# Chime_PCB_v2.net
KiCad netlist of a schematic drawn in EAGLE
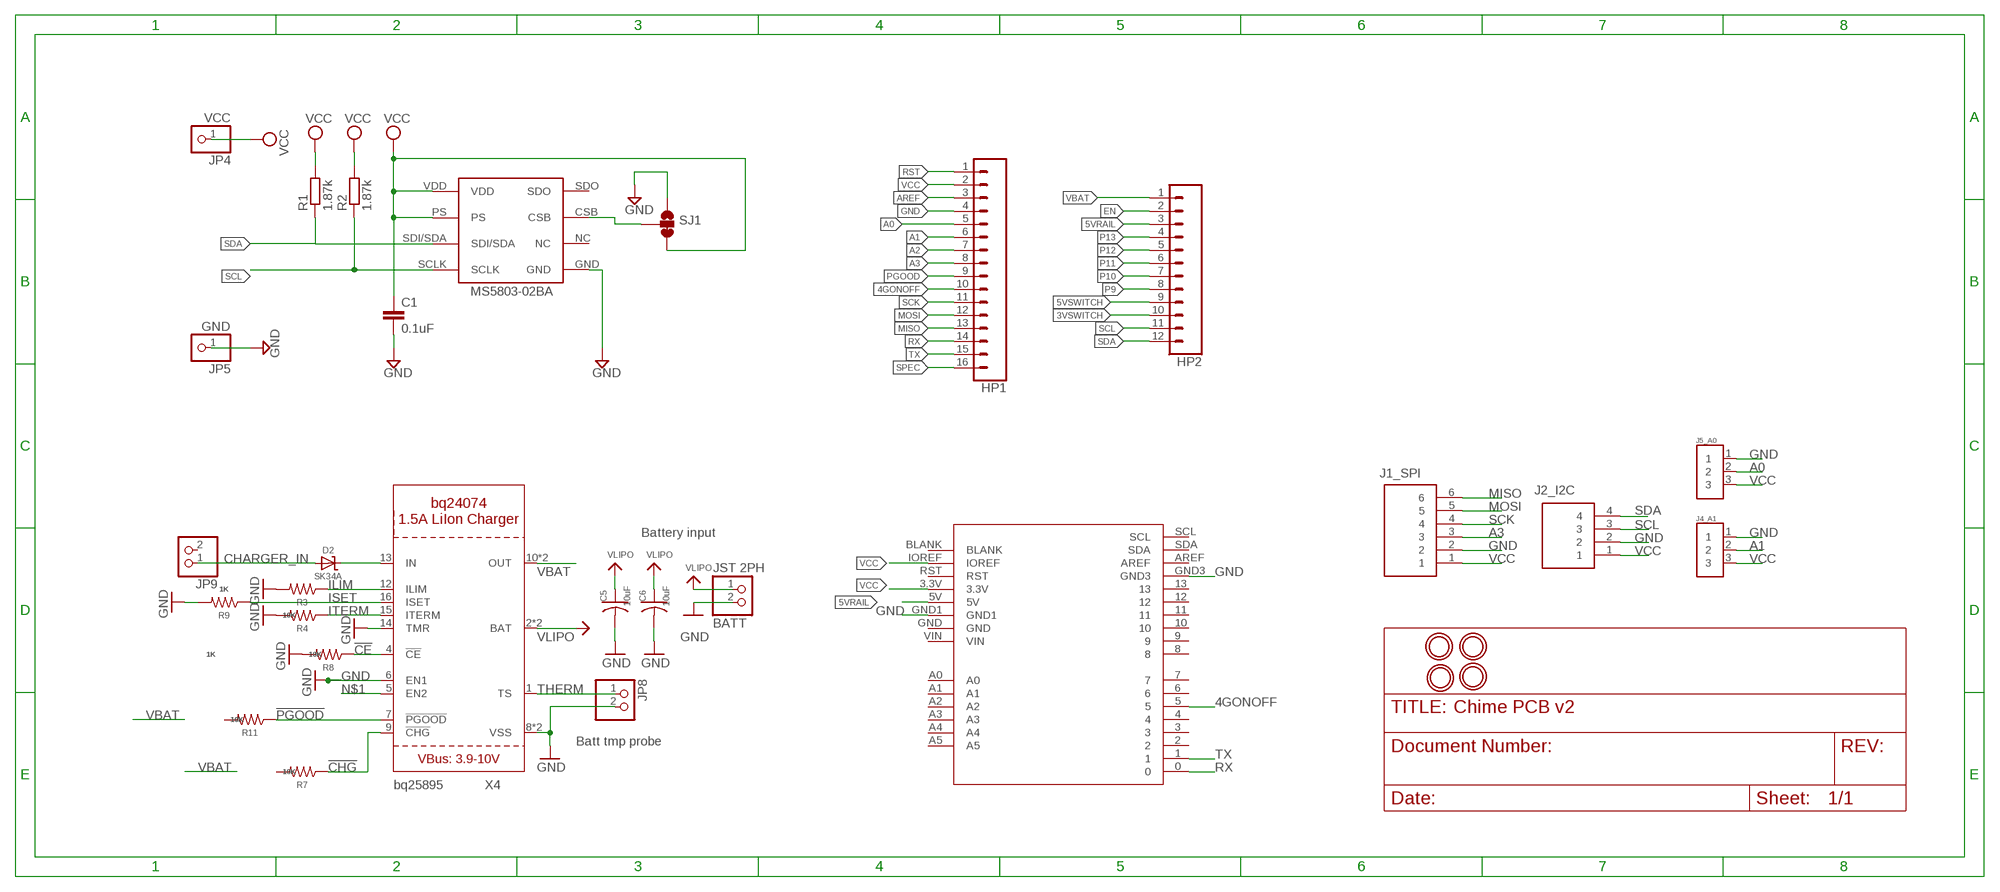
[diagram p0: schematic, sheet 1]

(export (version "E")
  (design (tool "Eeschema 10.0.6"))
  (components
    (comp (ref "BATT")
      (value "JST 2PH")
      (footprint "eagle-import:JST-PH-2-SMT-RA")
      (libsource (lib "eagle-import") (part "JST_2PIN-SMT-RA"))
    )
    (comp (ref "C1")
      (value "0.1uF")
      (footprint "eagle-import:C0805")
      (libsource (lib "eagle-import") (part "C-EUC0805"))
    )
    (comp (ref "C5")
      (value "10uF")
      (footprint "eagle-import:C0805K")
      (libsource (lib "eagle-import") (part "C-USC0805K"))
    )
    (comp (ref "C6")
      (value "10uF")
      (footprint "eagle-import:C0805K")
      (libsource (lib "eagle-import") (part "C-USC0805K"))
    )
    (comp (ref "D2")
      (value "SK34A")
      (footprint "eagle-import:SMADIODE")
      (libsource (lib "eagle-import") (part "DIODE-SCHOTTKYSMA"))
    )
    (comp (ref "HP1")
      (value "CONN_16")
      (footprint "eagle-import:1X16")
      (libsource (lib "eagle-import") (part "CONN_16"))
    )
    (comp (ref "HP2")
      (value "CONN_12")
      (footprint "eagle-import:1X12")
      (libsource (lib "eagle-import") (part "CONN_12"))
    )
    (comp (ref "J1_SPI")
      (value "1725698")
      (footprint "eagle-import:1725698")
      (fields (field (name "MOUSER_PART_NUMBER") "651-1725698"))
      (libsource (lib "eagle-import") (part "1725698"))
    )
    (comp (ref "J2_I2C")
      (value "1725672")
      (footprint "eagle-import:1725672")
      (fields (field (name "MOUSER_PART_NUMBER") "651-1725672"))
      (libsource (lib "eagle-import") (part "1725672"))
    )
    (comp (ref "J4_A1")
      (value "282834-3")
      (footprint "eagle-import:TE_282834-3")
      (fields (field (name "MF") "TE Connectivity"))
      (libsource (lib "eagle-import") (part "282834-3"))
    )
    (comp (ref "J5_A0")
      (value "282834-3")
      (footprint "eagle-import:TE_282834-3")
      (fields (field (name "MF") "TE Connectivity"))
      (libsource (lib "eagle-import") (part "282834-3"))
    )
    (comp (ref "JP4")
      (value "VCC")
      (footprint "eagle-import:1X01")
      (libsource (lib "eagle-import") (part "PINHD-1X1"))
    )
    (comp (ref "JP5")
      (value "GND")
      (footprint "eagle-import:1X01")
      (libsource (lib "eagle-import") (part "PINHD-1X1"))
    )
    (comp (ref "JP8")
      (value "PINHD-1X2")
      (footprint "eagle-import:1X02")
      (libsource (lib "eagle-import") (part "PINHD-1X2"))
    )
    (comp (ref "JP9")
      (value "PINHD-1X2")
      (footprint "eagle-import:1X02")
      (libsource (lib "eagle-import") (part "PINHD-1X2"))
    )
    (comp (ref "R1")
      (value "1.87k")
      (footprint "eagle-import:R0805")
      (libsource (lib "eagle-import") (part "R-EU_R0805"))
    )
    (comp (ref "R2")
      (value "1.87k")
      (footprint "eagle-import:R0805")
      (libsource (lib "eagle-import") (part "R-EU_R0805"))
    )
    (comp (ref "R3")
      (value "1K")
      (footprint "eagle-import:M0805")
      (libsource (lib "eagle-import") (part "R-US_M0805"))
    )
    (comp (ref "R4")
      (value "10K")
      (footprint "eagle-import:M0805")
      (libsource (lib "eagle-import") (part "R-US_M0805"))
    )
    (comp (ref "R7")
      (value "10K")
      (footprint "eagle-import:M0805")
      (libsource (lib "eagle-import") (part "R-US_M0805"))
    )
    (comp (ref "R8")
      (value "10K")
      (footprint "eagle-import:M0805")
      (libsource (lib "eagle-import") (part "R-US_M0805"))
    )
    (comp (ref "R9")
      (value "1K")
      (footprint "eagle-import:M0805")
      (libsource (lib "eagle-import") (part "R-US_M0805"))
    )
    (comp (ref "R11")
      (value "10K")
      (footprint "eagle-import:M0805")
      (libsource (lib "eagle-import") (part "R-US_M0805"))
    )
    (comp (ref "SJ1")
      (value "JUMPER-SMT_3_1-NC_TRACE_SILK")
      (footprint "eagle-import:SMT-JUMPER_3_1-NC_TRACE_SILK")
      (libsource (lib "eagle-import") (part "JUMPER-SMT_3_1-NC_TRACE_SILK"))
    )
    (comp (ref "U$1")
      (value "LTE_BOARD")
      (footprint "eagle-import:LTE_BOARD_FOOTPRINT")
      (libsource (lib "eagle-import") (part "LTE_BOARD"))
    )
    (comp (ref "U$2")
      (value "MOUNTINGHOLE2.5")
      (footprint "eagle-import:MOUNTINGHOLE_2.5_PLATED")
      (libsource (lib "eagle-import") (part "MOUNTINGHOLE2.5"))
    )
    (comp (ref "U$3")
      (value "MOUNTINGHOLE2.5")
      (footprint "eagle-import:MOUNTINGHOLE_2.5_PLATED")
      (libsource (lib "eagle-import") (part "MOUNTINGHOLE2.5"))
    )
    (comp (ref "U$4")
      (value "MOUNTINGHOLE2.5")
      (footprint "eagle-import:MOUNTINGHOLE_2.5_PLATED")
      (libsource (lib "eagle-import") (part "MOUNTINGHOLE2.5"))
    )
    (comp (ref "U$5")
      (value "MOUNTINGHOLE2.5")
      (footprint "eagle-import:MOUNTINGHOLE_2.5_PLATED")
      (libsource (lib "eagle-import") (part "MOUNTINGHOLE2.5"))
    )
    (comp (ref "U1")
      (value "MS5803-02BA")
      (footprint "eagle-import:MS5803-02BA")
      (libsource (lib "eagle-import") (part "MS5803-02BA"))
    )
    (comp (ref "X4")
      (value "BQ24074")
      (footprint "eagle-import:QFN16_3MM")
      (libsource (lib "eagle-import") (part "BQ24074"))
    )
  )
  (nets
    (net (code "1") (name "/CHARGER_IN") (class "Default")
      (node (ref "D2") (pin "A") (pinfunction "A_A") (pintype "passive"))
      (node (ref "JP9") (pin "1") (pinfunction "1_1") (pintype "passive"))
    )
    (net (code "2") (name "/ILIM") (class "Default")
      (node (ref "R3") (pin "1") (pinfunction "1_1") (pintype "passive"))
      (node (ref "X4") (pin "12") (pinfunction "ILIM_12") (pintype "input"))
    )
    (net (code "3") (name "/ISET") (class "Default")
      (node (ref "R9") (pin "1") (pinfunction "1_1") (pintype "passive"))
      (node (ref "X4") (pin "16") (pinfunction "ISET_16") (pintype "input"))
    )
    (net (code "4") (name "/ITERM") (class "Default")
      (node (ref "R4") (pin "1") (pinfunction "1_1") (pintype "passive"))
      (node (ref "X4") (pin "15") (pinfunction "ITERM_15") (pintype "input"))
    )
    (net (code "5") (name "/N$1") (class "Default")
      (node (ref "X4") (pin "5") (pinfunction "EN2_5") (pintype "input"))
    )
    (net (code "6") (name "/THERM") (class "Default")
      (node (ref "JP8") (pin "1") (pinfunction "1_1") (pintype "passive"))
      (node (ref "X4") (pin "1") (pinfunction "TS_1") (pintype "input"))
    )
    (net (code "7") (name "/~{CE}") (class "Default")
      (node (ref "R8") (pin "1") (pinfunction "1_1") (pintype "passive"))
      (node (ref "X4") (pin "4") (pinfunction "~{CE}_4") (pintype "input"))
    )
    (net (code "8") (name "/~{CHG}") (class "Default")
      (node (ref "R7") (pin "1") (pinfunction "1_1") (pintype "passive"))
      (node (ref "X4") (pin "9") (pinfunction "~{CHG}_9") (pintype "output"))
    )
    (net (code "9") (name "/~{PGOOD}") (class "Default")
      (node (ref "R11") (pin "1") (pinfunction "1_1") (pintype "passive"))
      (node (ref "X4") (pin "7") (pinfunction "~{PGOOD}_7") (pintype "output"))
    )
    (net (code "10") (name "3VSWITCH") (class "Default")
      (node (ref "HP2") (pin "10") (pinfunction "10_10") (pintype "passive"))
    )
    (net (code "11") (name "4GONOFF") (class "Default")
      (node (ref "HP1") (pin "10") (pinfunction "10_10") (pintype "passive"))
      (node (ref "U$1") (pin "5") (pinfunction "5_5") (pintype "bidirectional"))
    )
    (net (code "12") (name "5VRAIL") (class "Default")
      (node (ref "HP2") (pin "3") (pinfunction "3_3") (pintype "passive"))
      (node (ref "U$1") (pin "5V") (pinfunction "5V_5V") (pintype "bidirectional"))
    )
    (net (code "13") (name "5VSWITCH") (class "Default")
      (node (ref "HP2") (pin "9") (pinfunction "9_9") (pintype "passive"))
    )
    (net (code "14") (name "A0") (class "Default")
      (node (ref "HP1") (pin "5") (pinfunction "5_5") (pintype "passive"))
      (node (ref "J5_A0") (pin "2") (pinfunction "2_2") (pintype "passive"))
    )
    (net (code "15") (name "A1") (class "Default")
      (node (ref "HP1") (pin "6") (pinfunction "6_6") (pintype "passive"))
      (node (ref "J4_A1") (pin "2") (pinfunction "2_2") (pintype "passive"))
    )
    (net (code "16") (name "A2") (class "Default")
      (node (ref "HP1") (pin "7") (pinfunction "7_7") (pintype "passive"))
    )
    (net (code "17") (name "A3") (class "Default")
      (node (ref "HP1") (pin "8") (pinfunction "8_8") (pintype "passive"))
      (node (ref "J1_SPI") (pin "3") (pinfunction "3_3") (pintype "bidirectional"))
    )
    (net (code "18") (name "AREF") (class "Default")
      (node (ref "HP1") (pin "3") (pinfunction "3_3") (pintype "passive"))
    )
    (net (code "19") (name "EN") (class "Default")
      (node (ref "HP2") (pin "2") (pinfunction "2_2") (pintype "passive"))
    )
    (net (code "20") (name "GND") (class "Default")
      (node (ref "BATT") (pin "2") (pinfunction "1_2") (pintype "passive"))
      (node (ref "C1") (pin "2") (pinfunction "2_2") (pintype "passive"))
      (node (ref "C5") (pin "2") (pinfunction "2_2") (pintype "passive"))
      (node (ref "C6") (pin "2") (pinfunction "2_2") (pintype "passive"))
      (node (ref "HP1") (pin "4") (pinfunction "4_4") (pintype "passive"))
      (node (ref "J1_SPI") (pin "2") (pinfunction "2_2") (pintype "bidirectional"))
      (node (ref "J2_I2C") (pin "2") (pinfunction "2_2") (pintype "bidirectional"))
      (node (ref "J4_A1") (pin "1") (pinfunction "1_1") (pintype "passive"))
      (node (ref "J5_A0") (pin "1") (pinfunction "1_1") (pintype "passive"))
      (node (ref "JP5") (pin "1") (pinfunction "1_1") (pintype "passive"))
      (node (ref "JP8") (pin "2") (pinfunction "2_2") (pintype "passive"))
      (node (ref "R3") (pin "2") (pinfunction "2_2") (pintype "passive"))
      (node (ref "R4") (pin "2") (pinfunction "2_2") (pintype "passive"))
      (node (ref "R8") (pin "2") (pinfunction "2_2") (pintype "passive"))
      (node (ref "R9") (pin "2") (pinfunction "2_2") (pintype "passive"))
      (node (ref "SJ1") (pin "1") (pinfunction "1_1") (pintype "passive"))
      (node (ref "U$1") (pin "GND1") (pinfunction "GND1_GND1") (pintype "bidirectional"))
      (node (ref "U$1") (pin "GND3") (pinfunction "GND3_GND3") (pintype "bidirectional"))
      (node (ref "U1") (pin "GND") (pinfunction "GND_GND") (pintype "bidirectional"))
      (node (ref "X4") (pin "14") (pinfunction "TMR_14") (pintype "input"))
      (node (ref "X4") (pin "6") (pinfunction "EN1_6") (pintype "input"))
      (node (ref "X4") (pin "8") (pinfunction "VSS_8") (pintype "power_in"))
      (node (ref "X4") (pin "THERMAL") (pinfunction "VSS_THERMAL") (pintype "power_in"))
    )
    (net (code "21") (name "MISO") (class "Default")
      (node (ref "HP1") (pin "13") (pinfunction "13_13") (pintype "passive"))
      (node (ref "J1_SPI") (pin "6") (pinfunction "6_6") (pintype "bidirectional"))
    )
    (net (code "22") (name "MOSI") (class "Default")
      (node (ref "HP1") (pin "12") (pinfunction "12_12") (pintype "passive"))
      (node (ref "J1_SPI") (pin "5") (pinfunction "5_5") (pintype "bidirectional"))
    )
    (net (code "23") (name "Net-(SJ1-Pad2)") (class "Default")
      (node (ref "SJ1") (pin "2") (pinfunction "2_2") (pintype "passive"))
      (node (ref "U1") (pin "CSB") (pinfunction "CSB_CSB") (pintype "bidirectional"))
    )
    (net (code "24") (name "Net-(X4-IN)") (class "Default")
      (node (ref "D2") (pin "C") (pinfunction "C_C") (pintype "passive"))
      (node (ref "X4") (pin "13") (pinfunction "IN_13") (pintype "power_in"))
    )
    (net (code "25") (name "P9") (class "Default")
      (node (ref "HP2") (pin "8") (pinfunction "8_8") (pintype "passive"))
    )
    (net (code "26") (name "P10") (class "Default")
      (node (ref "HP2") (pin "7") (pinfunction "7_7") (pintype "passive"))
    )
    (net (code "27") (name "P11") (class "Default")
      (node (ref "HP2") (pin "6") (pinfunction "6_6") (pintype "passive"))
    )
    (net (code "28") (name "P12") (class "Default")
      (node (ref "HP2") (pin "5") (pinfunction "5_5") (pintype "passive"))
    )
    (net (code "29") (name "P13") (class "Default")
      (node (ref "HP2") (pin "4") (pinfunction "4_4") (pintype "passive"))
    )
    (net (code "30") (name "PGOOD") (class "Default")
      (node (ref "HP1") (pin "9") (pinfunction "9_9") (pintype "passive"))
    )
    (net (code "31") (name "RST") (class "Default")
      (node (ref "HP1") (pin "1") (pinfunction "1_1") (pintype "passive"))
    )
    (net (code "32") (name "RX") (class "Default")
      (node (ref "HP1") (pin "14") (pinfunction "14_14") (pintype "passive"))
      (node (ref "U$1") (pin "0") (pinfunction "0_0") (pintype "bidirectional"))
    )
    (net (code "33") (name "SCK") (class "Default")
      (node (ref "HP1") (pin "11") (pinfunction "11_11") (pintype "passive"))
      (node (ref "J1_SPI") (pin "4") (pinfunction "4_4") (pintype "bidirectional"))
    )
    (net (code "34") (name "SCL") (class "Default")
      (node (ref "HP2") (pin "11") (pinfunction "11_11") (pintype "passive"))
      (node (ref "J2_I2C") (pin "3") (pinfunction "3_3") (pintype "bidirectional"))
      (node (ref "R2") (pin "1") (pinfunction "1_1") (pintype "passive"))
      (node (ref "U1") (pin "SCLK") (pinfunction "SCLK_SCLK") (pintype "bidirectional"))
    )
    (net (code "35") (name "SDA") (class "Default")
      (node (ref "HP2") (pin "12") (pinfunction "12_12") (pintype "passive"))
      (node (ref "J2_I2C") (pin "4") (pinfunction "4_4") (pintype "bidirectional"))
      (node (ref "R1") (pin "1") (pinfunction "1_1") (pintype "passive"))
      (node (ref "U1") (pin "SDI/SDA") (pinfunction "SDI/SDA_SDI/SDA") (pintype "bidirectional"))
    )
    (net (code "36") (name "SPEC") (class "Default")
      (node (ref "HP1") (pin "16") (pinfunction "16_16") (pintype "passive"))
    )
    (net (code "37") (name "TX") (class "Default")
      (node (ref "HP1") (pin "15") (pinfunction "15_15") (pintype "passive"))
      (node (ref "U$1") (pin "1") (pinfunction "1_1") (pintype "bidirectional"))
    )
    (net (code "38") (name "VBAT") (class "Default")
      (node (ref "HP2") (pin "1") (pinfunction "1_1") (pintype "passive"))
      (node (ref "X4") (pin "10") (pinfunction "OUT_10") (pintype "output"))
      (node (ref "X4") (pin "11") (pinfunction "OUT_11") (pintype "output"))
    )
    (net (code "39") (name "VCC") (class "Default")
      (node (ref "C1") (pin "1") (pinfunction "1_1") (pintype "passive"))
      (node (ref "HP1") (pin "2") (pinfunction "2_2") (pintype "passive"))
      (node (ref "J1_SPI") (pin "1") (pinfunction "1_1") (pintype "bidirectional"))
      (node (ref "J2_I2C") (pin "1") (pinfunction "1_1") (pintype "bidirectional"))
      (node (ref "J4_A1") (pin "3") (pinfunction "3_3") (pintype "passive"))
      (node (ref "J5_A0") (pin "3") (pinfunction "3_3") (pintype "passive"))
      (node (ref "JP4") (pin "1") (pinfunction "1_1") (pintype "passive"))
      (node (ref "R1") (pin "2") (pinfunction "2_2") (pintype "passive"))
      (node (ref "R2") (pin "2") (pinfunction "2_2") (pintype "passive"))
      (node (ref "SJ1") (pin "3") (pinfunction "3_3") (pintype "passive"))
      (node (ref "U$1") (pin "3.3V") (pinfunction "3.3V_3.3V") (pintype "bidirectional"))
      (node (ref "U$1") (pin "IOREF") (pinfunction "IOREF_IOREF") (pintype "bidirectional"))
      (node (ref "U1") (pin "PS") (pinfunction "PS_PS") (pintype "bidirectional"))
      (node (ref "U1") (pin "VDD") (pinfunction "VDD_VDD") (pintype "bidirectional"))
    )
    (net (code "40") (name "VLIPO") (class "Default")
      (node (ref "BATT") (pin "1") (pinfunction "2_1") (pintype "passive"))
      (node (ref "C5") (pin "1") (pinfunction "1_1") (pintype "passive"))
      (node (ref "C6") (pin "1") (pinfunction "1_1") (pintype "passive"))
      (node (ref "X4") (pin "2") (pinfunction "BAT_2") (pintype "input"))
      (node (ref "X4") (pin "3") (pinfunction "BAT_3") (pintype "input"))
    )
    (net (code "41") (name "unconnected-(JP9-Pad2)") (class "Default")
      (node (ref "JP9") (pin "2") (pinfunction "2_2") (pintype "passive"))
    )
    (net (code "42") (name "unconnected-(R7-Pad2)") (class "Default")
      (node (ref "R7") (pin "2") (pinfunction "2_2") (pintype "passive"))
    )
    (net (code "43") (name "unconnected-(R11-Pad2)") (class "Default")
      (node (ref "R11") (pin "2") (pinfunction "2_2") (pintype "passive"))
    )
    (net (code "44") (name "unconnected-(U$1-Pad2)") (class "Default")
      (node (ref "U$1") (pin "2") (pinfunction "2_2") (pintype "bidirectional"))
    )
    (net (code "45") (name "unconnected-(U$1-Pad3)") (class "Default")
      (node (ref "U$1") (pin "3") (pinfunction "3_3") (pintype "bidirectional"))
    )
    (net (code "46") (name "unconnected-(U$1-Pad4)") (class "Default")
      (node (ref "U$1") (pin "4") (pinfunction "4_4") (pintype "bidirectional"))
    )
    (net (code "47") (name "unconnected-(U$1-Pad6)") (class "Default")
      (node (ref "U$1") (pin "6") (pinfunction "6_6") (pintype "bidirectional"))
    )
    (net (code "48") (name "unconnected-(U$1-Pad7)") (class "Default")
      (node (ref "U$1") (pin "7") (pinfunction "7_7") (pintype "bidirectional"))
    )
    (net (code "49") (name "unconnected-(U$1-Pad8)") (class "Default")
      (node (ref "U$1") (pin "8") (pinfunction "8_8") (pintype "bidirectional"))
    )
    (net (code "50") (name "unconnected-(U$1-Pad9)") (class "Default")
      (node (ref "U$1") (pin "9") (pinfunction "9_9") (pintype "bidirectional"))
    )
    (net (code "51") (name "unconnected-(U$1-Pad10)") (class "Default")
      (node (ref "U$1") (pin "10") (pinfunction "10_10") (pintype "bidirectional"))
    )
    (net (code "52") (name "unconnected-(U$1-Pad11)") (class "Default")
      (node (ref "U$1") (pin "11") (pinfunction "11_11") (pintype "bidirectional"))
    )
    (net (code "53") (name "unconnected-(U$1-Pad12)") (class "Default")
      (node (ref "U$1") (pin "12") (pinfunction "12_12") (pintype "bidirectional"))
    )
    (net (code "54") (name "unconnected-(U$1-Pad13)") (class "Default")
      (node (ref "U$1") (pin "13") (pinfunction "13_13") (pintype "bidirectional"))
    )
    (net (code "55") (name "unconnected-(U$1-PadA0)") (class "Default")
      (node (ref "U$1") (pin "A0") (pinfunction "A0_A0") (pintype "bidirectional"))
    )
    (net (code "56") (name "unconnected-(U$1-PadA1)") (class "Default")
      (node (ref "U$1") (pin "A1") (pinfunction "A1_A1") (pintype "bidirectional"))
    )
    (net (code "57") (name "unconnected-(U$1-PadA2)") (class "Default")
      (node (ref "U$1") (pin "A2") (pinfunction "A2_A2") (pintype "bidirectional"))
    )
    (net (code "58") (name "unconnected-(U$1-PadA3)") (class "Default")
      (node (ref "U$1") (pin "A3") (pinfunction "A3_A3") (pintype "bidirectional"))
    )
    (net (code "59") (name "unconnected-(U$1-PadA4)") (class "Default")
      (node (ref "U$1") (pin "A4") (pinfunction "A4_A4") (pintype "bidirectional"))
    )
    (net (code "60") (name "unconnected-(U$1-PadA5)") (class "Default")
      (node (ref "U$1") (pin "A5") (pinfunction "A5_A5") (pintype "bidirectional"))
    )
    (net (code "61") (name "unconnected-(U$1-PadAREF)") (class "Default")
      (node (ref "U$1") (pin "AREF") (pinfunction "AREF_AREF") (pintype "bidirectional"))
    )
    (net (code "62") (name "unconnected-(U$1-PadBLANK)") (class "Default")
      (node (ref "U$1") (pin "BLANK") (pinfunction "BLANK_BLANK") (pintype "bidirectional"))
    )
    (net (code "63") (name "unconnected-(U$1-PadGND)") (class "Default")
      (node (ref "U$1") (pin "GND") (pinfunction "GND_GND") (pintype "bidirectional"))
    )
    (net (code "64") (name "unconnected-(U$1-PadRST)") (class "Default")
      (node (ref "U$1") (pin "RST") (pinfunction "RST_RST") (pintype "bidirectional"))
    )
    (net (code "65") (name "unconnected-(U$1-PadSCL)") (class "Default")
      (node (ref "U$1") (pin "SCL") (pinfunction "SCL_SCL") (pintype "bidirectional"))
    )
    (net (code "66") (name "unconnected-(U$1-PadSDA)") (class "Default")
      (node (ref "U$1") (pin "SDA") (pinfunction "SDA_SDA") (pintype "bidirectional"))
    )
    (net (code "67") (name "unconnected-(U$1-PadVIN)") (class "Default")
      (node (ref "U$1") (pin "VIN") (pinfunction "VIN_VIN") (pintype "bidirectional"))
    )
    (net (code "68") (name "unconnected-(U1-PadNC)") (class "Default")
      (node (ref "U1") (pin "NC") (pinfunction "NC_NC") (pintype "bidirectional"))
    )
    (net (code "69") (name "unconnected-(U1-PadSDO)") (class "Default")
      (node (ref "U1") (pin "SDO") (pinfunction "SDO_SDO") (pintype "bidirectional"))
    )
  )
)
